# SEQ.net
KiCad netlist of a schematic drawn in Altium Designer
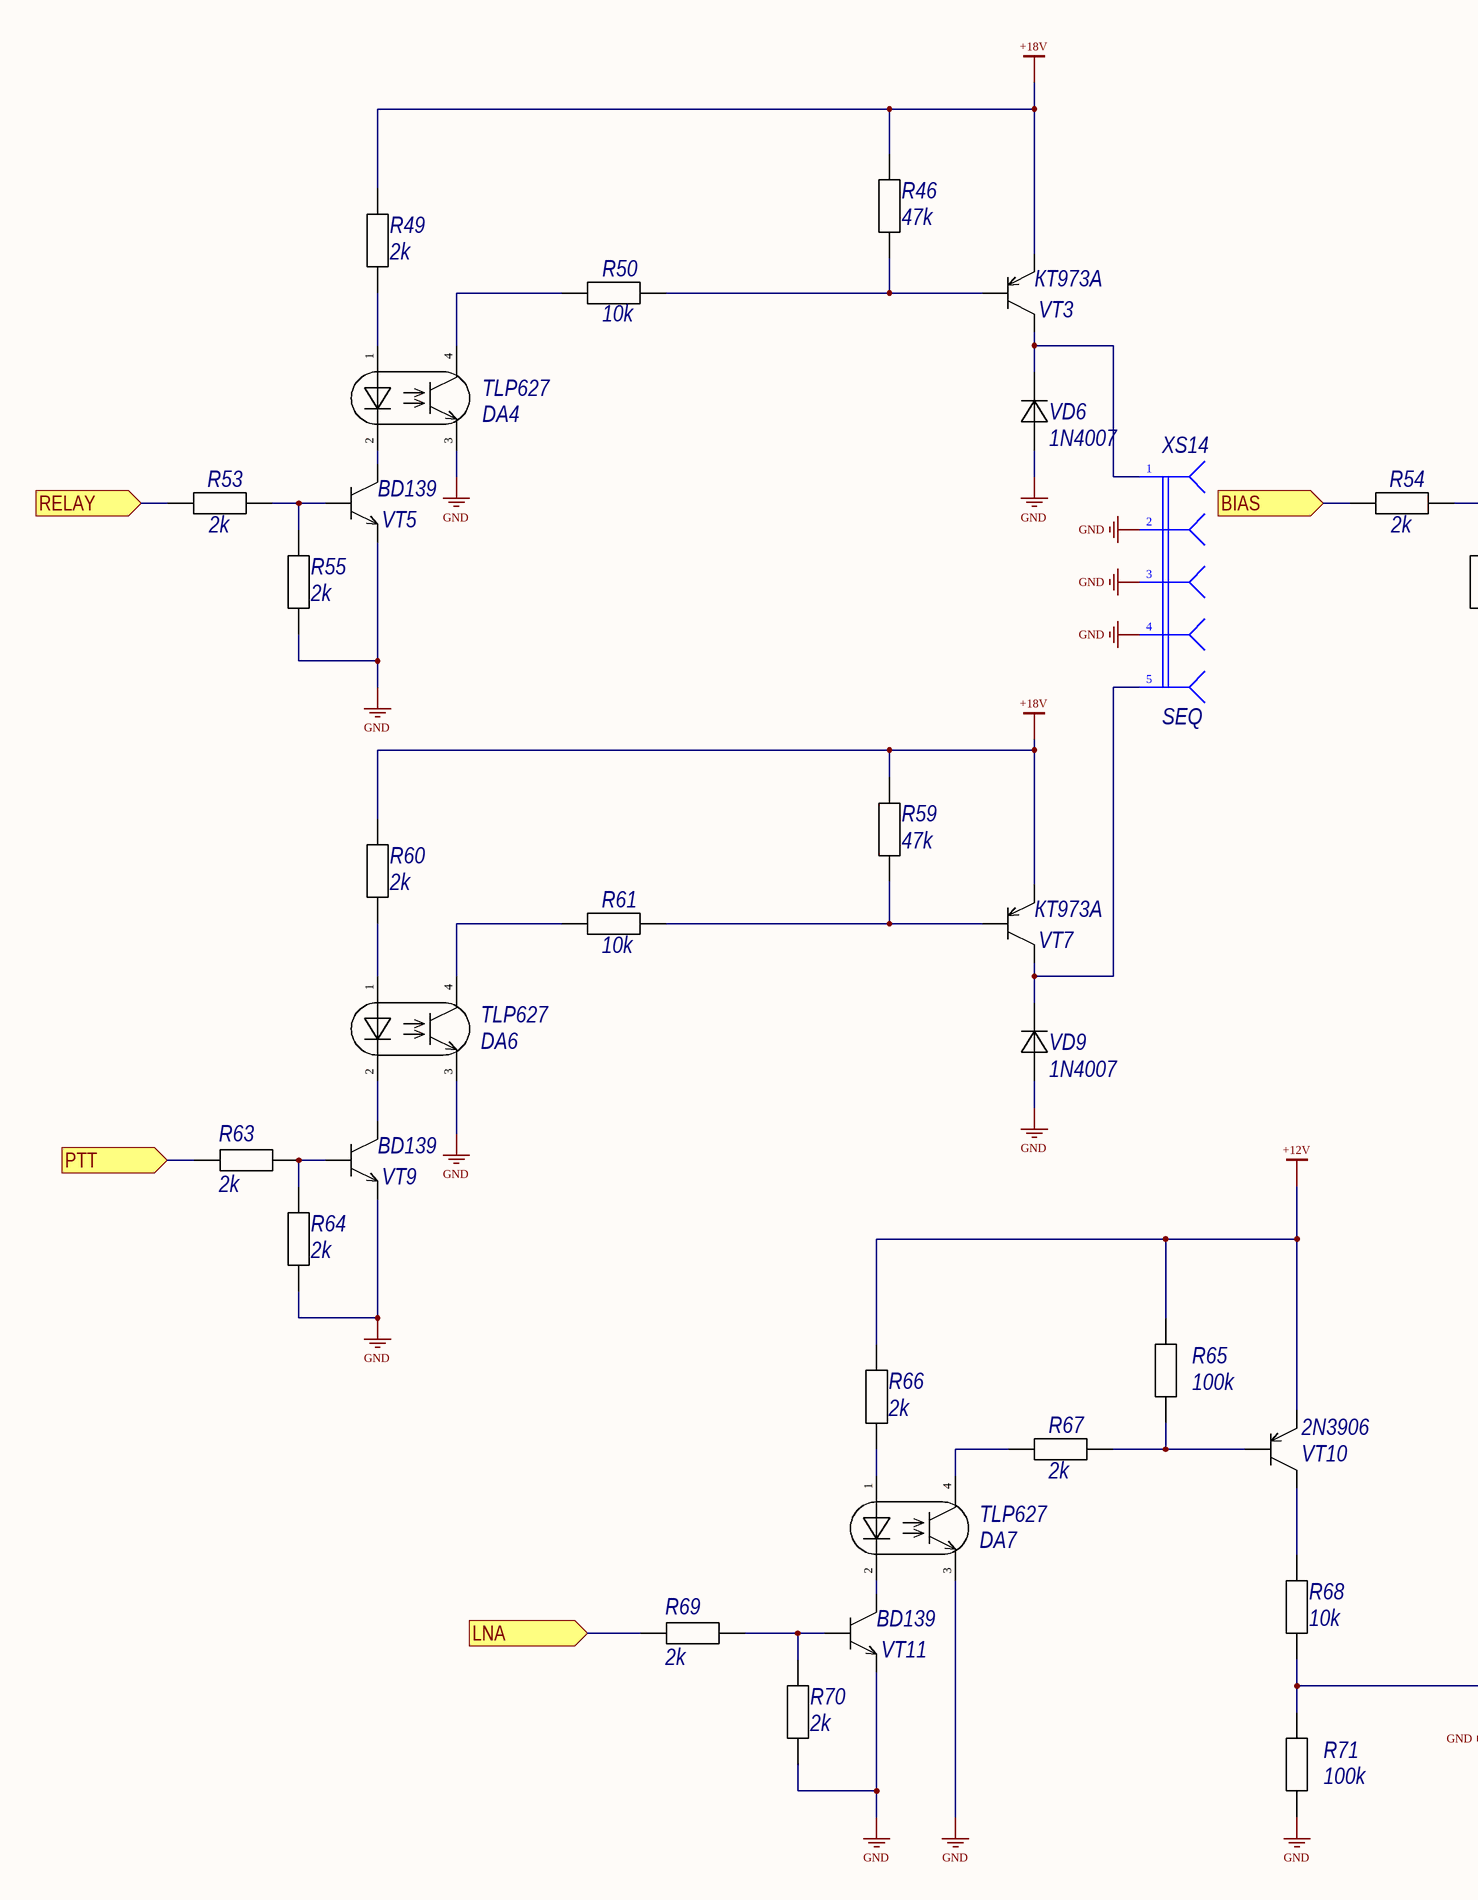
[diagram p0: SEQ.SchDoc, left]
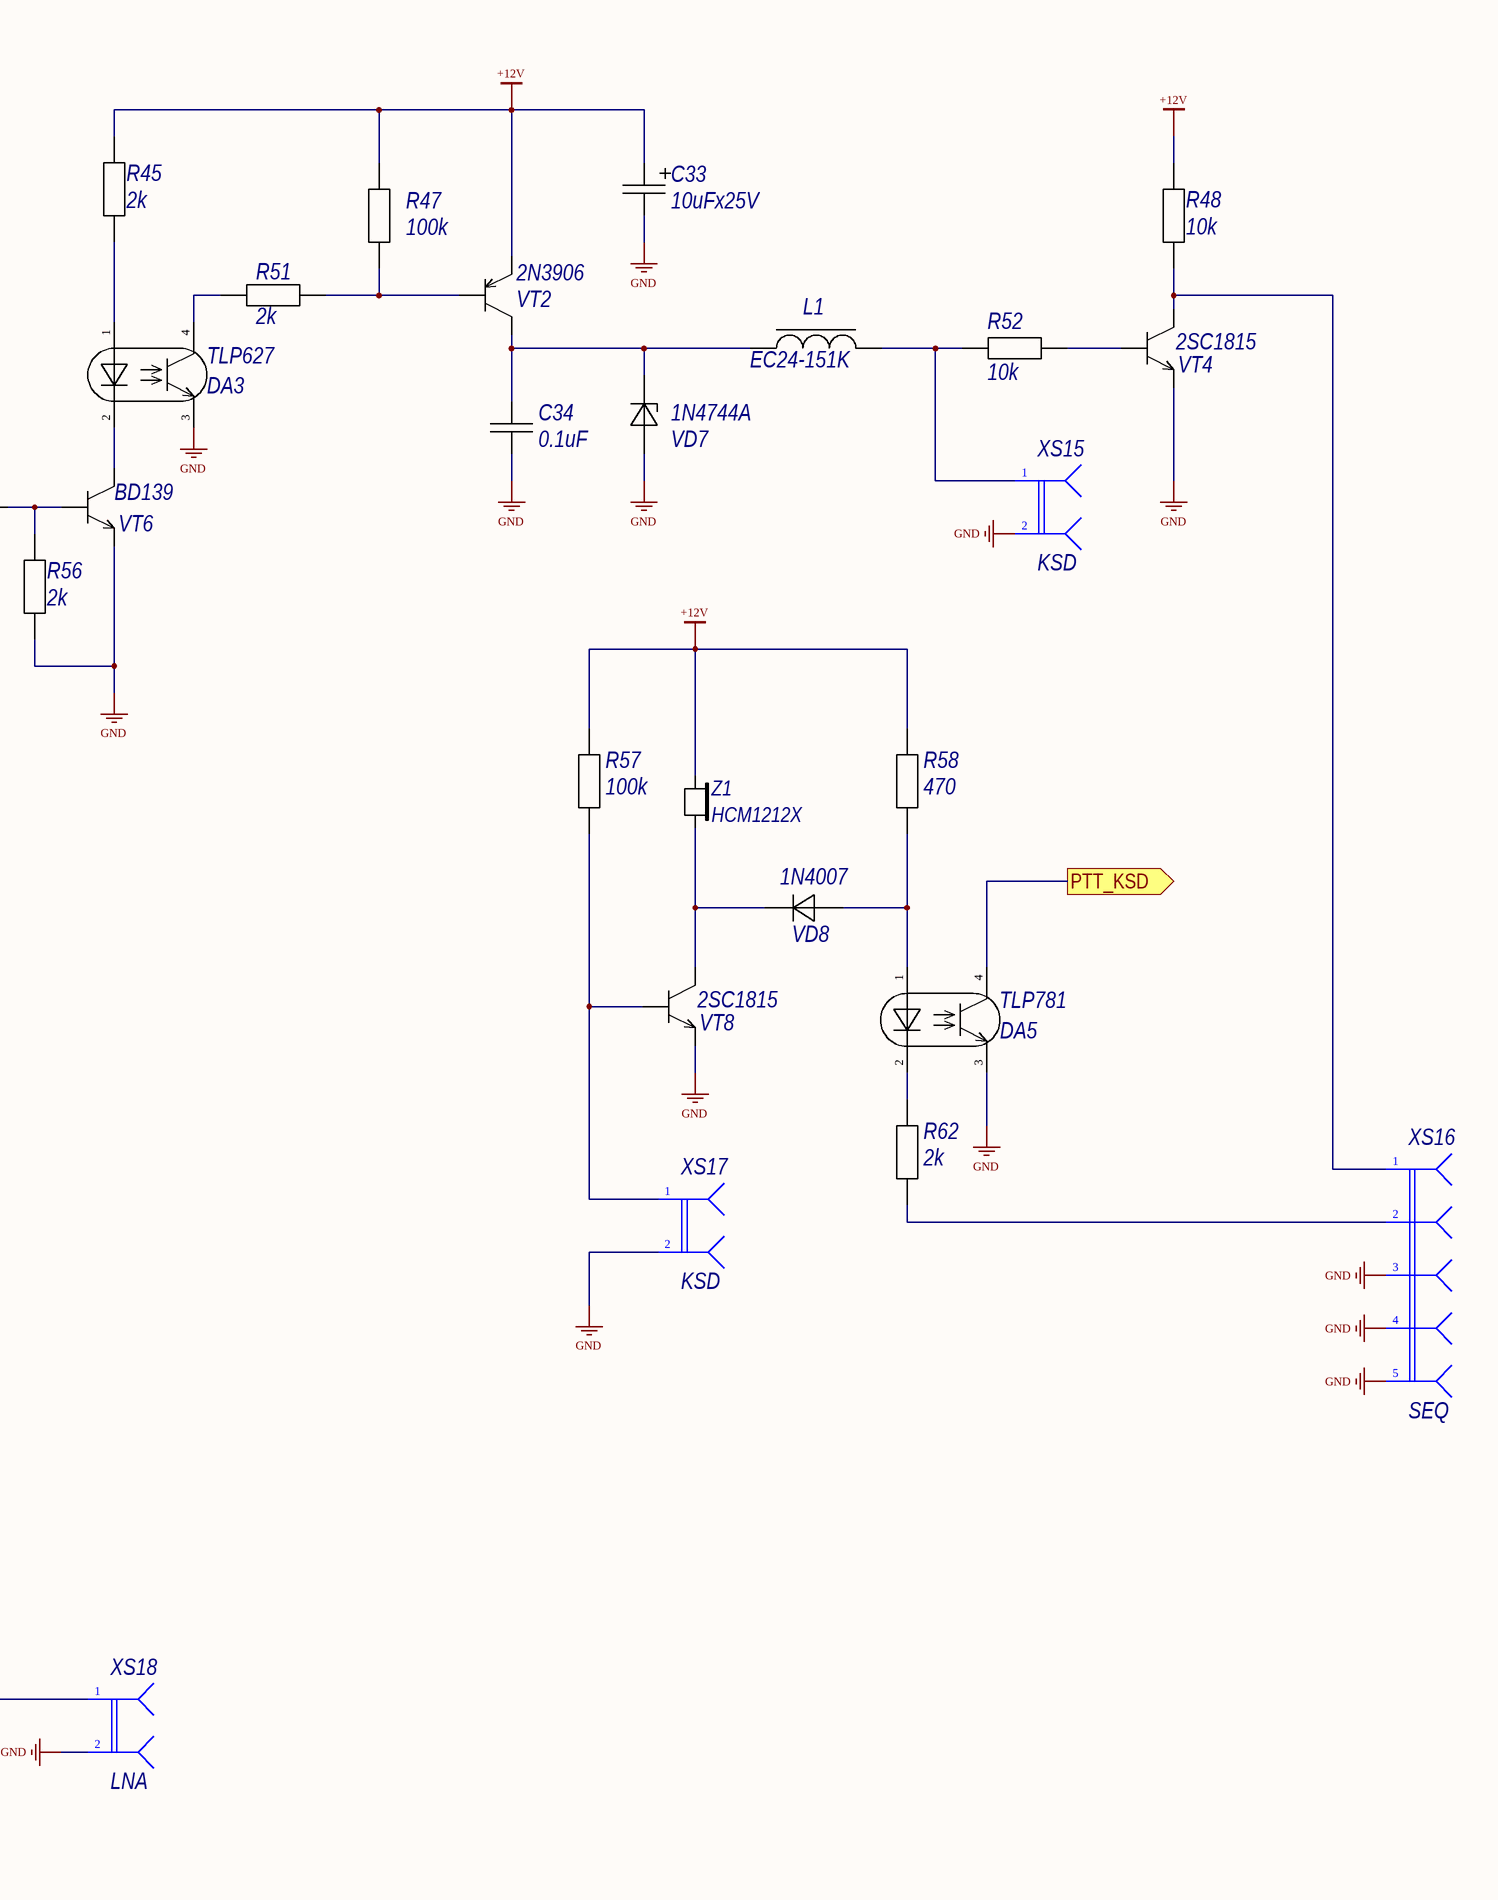
[diagram p1: SEQ.SchDoc, right]

(export (version "E")
  (design (tool "Eeschema 10.0.6"))
  (components
    (comp (ref "C33")
      (value "10uFx25V")
      (footprint "TECAP_A")
      (fields (field (name "PUBLISHER") "Andrew Danich"))
      (libsource (lib "PA_control_board") (part "CAP_TECAP_A"))
    )
    (comp (ref "C34")
      (value "0.1uF")
      (footprint "C0805C")
      (fields (field (name "PUBLISHER") "Andrew Danich"))
      (libsource (lib "PA_control_board") (part "CAP_0805"))
    )
    (comp (ref "DA3")
      (value "TLP627")
      (footprint "DIP-4")
      (fields (field (name "PUBLISHER") "Andrew Danich"))
      (libsource (lib "PA_control_board") (part "TLP627"))
    )
    (comp (ref "DA4")
      (value "TLP627")
      (footprint "DIP-4")
      (fields (field (name "PUBLISHER") "Andrew Danich"))
      (libsource (lib "PA_control_board") (part "TLP627"))
    )
    (comp (ref "DA5")
      (value "TLP781")
      (footprint "DIP-4")
      (fields (field (name "PUBLISHER") "Andrew Danich"))
      (libsource (lib "PA_control_board") (part "TLP781"))
    )
    (comp (ref "DA6")
      (value "TLP627")
      (footprint "DIP-4")
      (fields (field (name "PUBLISHER") "Andrew Danich"))
      (libsource (lib "PA_control_board") (part "TLP627"))
    )
    (comp (ref "DA7")
      (value "TLP627")
      (footprint "DIP-4")
      (fields (field (name "PUBLISHER") "Andrew Danich"))
      (libsource (lib "PA_control_board") (part "TLP627"))
    )
    (comp (ref "L1")
      (value "EC24-151K")
      (footprint "AXIAL-0.6")
      (fields (field (name "PUBLISHER") "Andrew Danich"))
      (libsource (lib "PA_control_board") (part "IND_BIAS"))
    )
    (comp (ref "R45")
      (value "2k")
      (footprint "AXIAL-0.6")
      (fields (field (name "PUBLISHER") "Andrew Danich"))
      (libsource (lib "PA_control_board") (part "RES_1W"))
    )
    (comp (ref "R46")
      (value "47k")
      (footprint "AXIAL-0.6")
      (fields (field (name "PUBLISHER") "Andrew Danich"))
      (libsource (lib "PA_control_board") (part "RES_1W"))
    )
    (comp (ref "R47")
      (value "100k")
      (footprint "AXIAL-0.6")
      (fields (field (name "PUBLISHER") "Andrew Danich"))
      (libsource (lib "PA_control_board") (part "RES_1W"))
    )
    (comp (ref "R48")
      (value "10k")
      (footprint "AXIAL-0.6")
      (fields (field (name "PUBLISHER") "Andrew Danich"))
      (libsource (lib "PA_control_board") (part "RES_1W"))
    )
    (comp (ref "R49")
      (value "2k")
      (footprint "AXIAL-0.6")
      (fields (field (name "PUBLISHER") "Andrew Danich"))
      (libsource (lib "PA_control_board") (part "RES_1W"))
    )
    (comp (ref "R50")
      (value "10k")
      (footprint "AXIAL-0.6")
      (fields (field (name "PUBLISHER") "Andrew Danich"))
      (libsource (lib "PA_control_board") (part "RES_1W"))
    )
    (comp (ref "R51")
      (value "2k")
      (footprint "AXIAL-0.6")
      (fields (field (name "PUBLISHER") "Andrew Danich"))
      (libsource (lib "PA_control_board") (part "RES_1W"))
    )
    (comp (ref "R52")
      (value "10k")
      (footprint "AXIAL-0.6")
      (fields (field (name "PUBLISHER") "Andrew Danich"))
      (libsource (lib "PA_control_board") (part "RES_1W"))
    )
    (comp (ref "R53")
      (value "2k")
      (footprint "AXIAL-0.6")
      (fields (field (name "PUBLISHER") "Andrew Danich"))
      (libsource (lib "PA_control_board") (part "RES_1W"))
    )
    (comp (ref "R54")
      (value "2k")
      (footprint "AXIAL-0.6")
      (fields (field (name "PUBLISHER") "Andrew Danich"))
      (libsource (lib "PA_control_board") (part "RES_1W"))
    )
    (comp (ref "R55")
      (value "2k")
      (footprint "AXIAL-0.6")
      (fields (field (name "PUBLISHER") "Andrew Danich"))
      (libsource (lib "PA_control_board") (part "RES_1W"))
    )
    (comp (ref "R56")
      (value "2k")
      (footprint "AXIAL-0.6")
      (fields (field (name "PUBLISHER") "Andrew Danich"))
      (libsource (lib "PA_control_board") (part "RES_1W"))
    )
    (comp (ref "R57")
      (value "100k")
      (footprint "AXIAL-0.6")
      (fields (field (name "PUBLISHER") "Andrew Danich"))
      (libsource (lib "PA_control_board") (part "RES_1W"))
    )
    (comp (ref "R58")
      (value "470")
      (footprint "AXIAL-0.6")
      (fields (field (name "PUBLISHER") "Andrew Danich"))
      (libsource (lib "PA_control_board") (part "RES_1W"))
    )
    (comp (ref "R59")
      (value "47k")
      (footprint "AXIAL-0.6")
      (fields (field (name "PUBLISHER") "Andrew Danich"))
      (libsource (lib "PA_control_board") (part "RES_1W"))
    )
    (comp (ref "R60")
      (value "2k")
      (footprint "AXIAL-0.6")
      (fields (field (name "PUBLISHER") "Andrew Danich"))
      (libsource (lib "PA_control_board") (part "RES_1W"))
    )
    (comp (ref "R61")
      (value "10k")
      (footprint "AXIAL-0.6")
      (fields (field (name "PUBLISHER") "Andrew Danich"))
      (libsource (lib "PA_control_board") (part "RES_1W"))
    )
    (comp (ref "R62")
      (value "2k")
      (footprint "AXIAL-0.6")
      (fields (field (name "PUBLISHER") "Andrew Danich"))
      (libsource (lib "PA_control_board") (part "RES_1W"))
    )
    (comp (ref "R63")
      (value "2k")
      (footprint "AXIAL-0.6")
      (fields (field (name "PUBLISHER") "Andrew Danich"))
      (libsource (lib "PA_control_board") (part "RES_1W"))
    )
    (comp (ref "R64")
      (value "2k")
      (footprint "AXIAL-0.6")
      (fields (field (name "PUBLISHER") "Andrew Danich"))
      (libsource (lib "PA_control_board") (part "RES_1W"))
    )
    (comp (ref "R65")
      (value "100k")
      (footprint "AXIAL-0.6")
      (fields (field (name "PUBLISHER") "Andrew Danich"))
      (libsource (lib "PA_control_board") (part "RES_1W"))
    )
    (comp (ref "R66")
      (value "2k")
      (footprint "AXIAL-0.6")
      (fields (field (name "PUBLISHER") "Andrew Danich"))
      (libsource (lib "PA_control_board") (part "RES_1W"))
    )
    (comp (ref "R67")
      (value "2k")
      (footprint "AXIAL-0.6")
      (fields (field (name "PUBLISHER") "Andrew Danich"))
      (libsource (lib "PA_control_board") (part "RES_1W"))
    )
    (comp (ref "R68")
      (value "10k")
      (footprint "AXIAL-0.6")
      (fields (field (name "PUBLISHER") "Andrew Danich"))
      (libsource (lib "PA_control_board") (part "RES_1W"))
    )
    (comp (ref "R69")
      (value "2k")
      (footprint "AXIAL-0.6")
      (fields (field (name "PUBLISHER") "Andrew Danich"))
      (libsource (lib "PA_control_board") (part "RES_1W"))
    )
    (comp (ref "R70")
      (value "2k")
      (footprint "AXIAL-0.6")
      (fields (field (name "PUBLISHER") "Andrew Danich"))
      (libsource (lib "PA_control_board") (part "RES_1W"))
    )
    (comp (ref "R71")
      (value "100k")
      (footprint "AXIAL-0.6")
      (fields (field (name "PUBLISHER") "Andrew Danich"))
      (libsource (lib "PA_control_board") (part "RES_1W"))
    )
    (comp (ref "VD6")
      (value "1N4007")
      (footprint "DO-41")
      (fields (field (name "PUBLISHER") "Andrew Danich"))
      (libsource (lib "PA_control_board") (part "1N4007"))
    )
    (comp (ref "VD7")
      (value "1N4744A")
      (footprint "DO-41")
      (fields (field (name "PUBLISHER") "Andrew Danich"))
      (libsource (lib "PA_control_board") (part "1N4744A"))
    )
    (comp (ref "VD8")
      (value "1N4007")
      (footprint "DO-41")
      (fields (field (name "PUBLISHER") "Andrew Danich"))
      (libsource (lib "PA_control_board") (part "1N4007"))
    )
    (comp (ref "VD9")
      (value "1N4007")
      (footprint "DO-41")
      (fields (field (name "PUBLISHER") "Andrew Danich"))
      (libsource (lib "PA_control_board") (part "1N4007"))
    )
    (comp (ref "VT2")
      (value "2N3906")
      (footprint "TO-92-A")
      (fields (field (name "PUBLISHER") "Andrew Danich"))
      (libsource (lib "PA_control_board") (part "2N3906"))
    )
    (comp (ref "VT3")
      (value "КТ973А")
      (footprint "TO-126")
      (fields (field (name "PUBLISHER") "Andrew Danich"))
      (libsource (lib "PA_control_board") (part "КТ973А"))
    )
    (comp (ref "VT4")
      (value "2SC1815")
      (footprint "TO-92-A")
      (fields (field (name "PUBLISHER") "Andrew Danich"))
      (libsource (lib "PA_control_board") (part "2SC1815"))
    )
    (comp (ref "VT5")
      (value "BD139")
      (footprint "TO-126")
      (fields (field (name "PUBLISHER") "Andrew Danich"))
      (libsource (lib "PA_control_board") (part "BD139"))
    )
    (comp (ref "VT6")
      (value "BD139")
      (footprint "TO-126")
      (fields (field (name "PUBLISHER") "Andrew Danich"))
      (libsource (lib "PA_control_board") (part "BD139"))
    )
    (comp (ref "VT7")
      (value "КТ973А")
      (footprint "TO-126")
      (fields (field (name "PUBLISHER") "Andrew Danich"))
      (libsource (lib "PA_control_board") (part "КТ973А"))
    )
    (comp (ref "VT8")
      (value "2SC1815")
      (footprint "TO-92-A")
      (fields (field (name "PUBLISHER") "Andrew Danich"))
      (libsource (lib "PA_control_board") (part "2SC1815"))
    )
    (comp (ref "VT9")
      (value "BD139")
      (footprint "TO-126")
      (fields (field (name "PUBLISHER") "Andrew Danich"))
      (libsource (lib "PA_control_board") (part "BD139"))
    )
    (comp (ref "VT10")
      (value "2N3906")
      (footprint "TO-92-A")
      (fields (field (name "PUBLISHER") "Andrew Danich"))
      (libsource (lib "PA_control_board") (part "2N3906"))
    )
    (comp (ref "VT11")
      (value "BD139")
      (footprint "TO-126")
      (fields (field (name "PUBLISHER") "Andrew Danich"))
      (libsource (lib "PA_control_board") (part "BD139"))
    )
    (comp (ref "XS14")
      (value "SEQ")
      (footprint "WF-5")
      (fields (field (name "PUBLISHER") "Andrew Danich"))
      (libsource (lib "PA_control_board") (part "CONNECT_SEQ"))
    )
    (comp (ref "XS15")
      (value "KSD")
      (footprint "WF-2")
      (fields (field (name "PUBLISHER") "Andrew Danich"))
      (libsource (lib "PA_control_board") (part "CONNECT_KSD"))
    )
    (comp (ref "XS16")
      (value "SEQ")
      (footprint "WF-5")
      (fields (field (name "PUBLISHER") "Andrew Danich"))
      (libsource (lib "PA_control_board") (part "CONNECT_SEQ"))
    )
    (comp (ref "XS17")
      (value "KSD")
      (footprint "WF-2")
      (fields (field (name "PUBLISHER") "Andrew Danich"))
      (libsource (lib "PA_control_board") (part "CONNECT_KSD"))
    )
    (comp (ref "XS18")
      (value "LNA")
      (footprint "WF-2")
      (fields (field (name "PUBLISHER") "Andrew Danich"))
      (libsource (lib "PA_control_board") (part "CONNECT_KSD"))
    )
    (comp (ref "Z1")
      (value "HCM1212X")
      (footprint "HCM1206X")
      (libsource (lib "PA_control_board") (part "HCM1212X"))
    )
  )
  (nets
    (net (code "1") (name "+12V") (class "Default")
      (node (ref "C33") (pin "1") (pinfunction "1_1") (pintype "passive"))
      (node (ref "R45") (pin "2") (pinfunction "2_2") (pintype "passive"))
      (node (ref "R47") (pin "1") (pinfunction "1_1") (pintype "passive"))
      (node (ref "R48") (pin "2") (pinfunction "2_2") (pintype "passive"))
      (node (ref "R57") (pin "2") (pinfunction "2_2") (pintype "passive"))
      (node (ref "R58") (pin "2") (pinfunction "2_2") (pintype "passive"))
      (node (ref "R65") (pin "1") (pinfunction "1_1") (pintype "passive"))
      (node (ref "R66") (pin "2") (pinfunction "2_2") (pintype "passive"))
      (node (ref "VT10") (pin "3") (pinfunction "Э_3") (pintype "passive"))
      (node (ref "VT2") (pin "3") (pinfunction "Э_3") (pintype "passive"))
      (node (ref "Z1") (pin "2") (pinfunction "2_2") (pintype "passive"))
    )
    (net (code "2") (name "+18V") (class "Default")
      (node (ref "R46") (pin "1") (pinfunction "1_1") (pintype "passive"))
      (node (ref "R49") (pin "2") (pinfunction "2_2") (pintype "passive"))
      (node (ref "R59") (pin "1") (pinfunction "1_1") (pintype "passive"))
      (node (ref "R60") (pin "2") (pinfunction "2_2") (pintype "passive"))
      (node (ref "VT3") (pin "3") (pinfunction "Э_3") (pintype "passive"))
      (node (ref "VT7") (pin "3") (pinfunction "Э_3") (pintype "passive"))
    )
    (net (code "3") (name "/BIAS") (class "Default")
      (node (ref "R54") (pin "2") (pinfunction "2_2") (pintype "passive"))
    )
    (net (code "4") (name "/LNA") (class "Default")
      (node (ref "R69") (pin "2") (pinfunction "2_2") (pintype "passive"))
    )
    (net (code "5") (name "/PTT") (class "Default")
      (node (ref "R63") (pin "2") (pinfunction "2_2") (pintype "passive"))
    )
    (net (code "6") (name "/PTT_KSD") (class "Default")
      (node (ref "DA5") (pin "4") (pinfunction "К_4") (pintype "passive"))
    )
    (net (code "7") (name "/RELAY") (class "Default")
      (node (ref "R53") (pin "2") (pinfunction "2_2") (pintype "passive"))
    )
    (net (code "8") (name "GND") (class "Default")
      (node (ref "C33") (pin "2") (pinfunction "2_2") (pintype "passive"))
      (node (ref "C34") (pin "2") (pinfunction "2_2") (pintype "passive"))
      (node (ref "DA3") (pin "3") (pinfunction "Э_3") (pintype "passive"))
      (node (ref "DA4") (pin "3") (pinfunction "Э_3") (pintype "passive"))
      (node (ref "DA5") (pin "3") (pinfunction "Э_3") (pintype "passive"))
      (node (ref "DA6") (pin "3") (pinfunction "Э_3") (pintype "passive"))
      (node (ref "DA7") (pin "3") (pinfunction "Э_3") (pintype "passive"))
      (node (ref "R55") (pin "1") (pinfunction "1_1") (pintype "passive"))
      (node (ref "R56") (pin "1") (pinfunction "1_1") (pintype "passive"))
      (node (ref "R64") (pin "1") (pinfunction "1_1") (pintype "passive"))
      (node (ref "R70") (pin "1") (pinfunction "1_1") (pintype "passive"))
      (node (ref "R71") (pin "2") (pinfunction "2_2") (pintype "passive"))
      (node (ref "VD6") (pin "2") (pinfunction "2_2") (pintype "passive"))
      (node (ref "VD7") (pin "1") (pinfunction "А_1") (pintype "passive"))
      (node (ref "VD9") (pin "2") (pinfunction "2_2") (pintype "passive"))
      (node (ref "VT11") (pin "3") (pinfunction "Э_3") (pintype "passive"))
      (node (ref "VT4") (pin "3") (pinfunction "Э_3") (pintype "passive"))
      (node (ref "VT5") (pin "3") (pinfunction "Э_3") (pintype "passive"))
      (node (ref "VT6") (pin "3") (pinfunction "Э_3") (pintype "passive"))
      (node (ref "VT8") (pin "3") (pinfunction "Э_3") (pintype "passive"))
      (node (ref "VT9") (pin "3") (pinfunction "Э_3") (pintype "passive"))
      (node (ref "XS14") (pin "2") (pintype "passive"))
      (node (ref "XS14") (pin "3") (pintype "passive"))
      (node (ref "XS14") (pin "4") (pintype "passive"))
      (node (ref "XS15") (pin "2") (pintype "passive"))
      (node (ref "XS16") (pin "3") (pintype "passive"))
      (node (ref "XS16") (pin "4") (pintype "passive"))
      (node (ref "XS16") (pin "5") (pintype "passive"))
      (node (ref "XS17") (pin "2") (pintype "passive"))
      (node (ref "XS18") (pin "2") (pintype "passive"))
    )
    (net (code "9") (name "Net-(DA3-CА)") (class "Default")
      (node (ref "DA3") (pin "1") (pinfunction "CА_1") (pintype "passive"))
      (node (ref "R45") (pin "1") (pinfunction "1_1") (pintype "passive"))
    )
    (net (code "10") (name "Net-(DA3-CК)") (class "Default")
      (node (ref "DA3") (pin "2") (pinfunction "CК_2") (pintype "passive"))
      (node (ref "VT6") (pin "2") (pinfunction "К_2") (pintype "passive"))
    )
    (net (code "11") (name "Net-(DA3-К)") (class "Default")
      (node (ref "DA3") (pin "4") (pinfunction "К_4") (pintype "passive"))
      (node (ref "R51") (pin "2") (pinfunction "2_2") (pintype "passive"))
    )
    (net (code "12") (name "Net-(DA4-CА)") (class "Default")
      (node (ref "DA4") (pin "1") (pinfunction "CА_1") (pintype "passive"))
      (node (ref "R49") (pin "1") (pinfunction "1_1") (pintype "passive"))
    )
    (net (code "13") (name "Net-(DA4-CК)") (class "Default")
      (node (ref "DA4") (pin "2") (pinfunction "CК_2") (pintype "passive"))
      (node (ref "VT5") (pin "2") (pinfunction "К_2") (pintype "passive"))
    )
    (net (code "14") (name "Net-(DA4-К)") (class "Default")
      (node (ref "DA4") (pin "4") (pinfunction "К_4") (pintype "passive"))
      (node (ref "R50") (pin "2") (pinfunction "2_2") (pintype "passive"))
    )
    (net (code "15") (name "Net-(DA5-CА)") (class "Default")
      (node (ref "DA5") (pin "1") (pinfunction "CА_1") (pintype "passive"))
      (node (ref "R58") (pin "1") (pinfunction "1_1") (pintype "passive"))
      (node (ref "VD8") (pin "2") (pinfunction "2_2") (pintype "passive"))
    )
    (net (code "16") (name "Net-(DA5-CК)") (class "Default")
      (node (ref "DA5") (pin "2") (pinfunction "CК_2") (pintype "passive"))
      (node (ref "R62") (pin "2") (pinfunction "2_2") (pintype "passive"))
    )
    (net (code "17") (name "Net-(DA6-CА)") (class "Default")
      (node (ref "DA6") (pin "1") (pinfunction "CА_1") (pintype "passive"))
      (node (ref "R60") (pin "1") (pinfunction "1_1") (pintype "passive"))
    )
    (net (code "18") (name "Net-(DA6-CК)") (class "Default")
      (node (ref "DA6") (pin "2") (pinfunction "CК_2") (pintype "passive"))
      (node (ref "VT9") (pin "2") (pinfunction "К_2") (pintype "passive"))
    )
    (net (code "19") (name "Net-(DA6-К)") (class "Default")
      (node (ref "DA6") (pin "4") (pinfunction "К_4") (pintype "passive"))
      (node (ref "R61") (pin "2") (pinfunction "2_2") (pintype "passive"))
    )
    (net (code "20") (name "Net-(DA7-CА)") (class "Default")
      (node (ref "DA7") (pin "1") (pinfunction "CА_1") (pintype "passive"))
      (node (ref "R66") (pin "1") (pinfunction "1_1") (pintype "passive"))
    )
    (net (code "21") (name "Net-(DA7-CК)") (class "Default")
      (node (ref "DA7") (pin "2") (pinfunction "CК_2") (pintype "passive"))
      (node (ref "VT11") (pin "2") (pinfunction "К_2") (pintype "passive"))
    )
    (net (code "22") (name "Net-(DA7-К)") (class "Default")
      (node (ref "DA7") (pin "4") (pinfunction "К_4") (pintype "passive"))
      (node (ref "R67") (pin "2") (pinfunction "2_2") (pintype "passive"))
    )
    (net (code "23") (name "Net-(L1-Pad2)") (class "Default")
      (node (ref "L1") (pin "2") (pinfunction "2_2") (pintype "passive"))
      (node (ref "R52") (pin "1") (pinfunction "1_1") (pintype "passive"))
      (node (ref "XS15") (pin "1") (pintype "passive"))
    )
    (net (code "24") (name "Net-(R62-Pad1)") (class "Default")
      (node (ref "R62") (pin "1") (pinfunction "1_1") (pintype "passive"))
      (node (ref "XS16") (pin "2") (pintype "passive"))
    )
    (net (code "25") (name "Net-(R68-Pad1)") (class "Default")
      (node (ref "R68") (pin "1") (pinfunction "1_1") (pintype "passive"))
      (node (ref "R71") (pin "1") (pinfunction "1_1") (pintype "passive"))
      (node (ref "XS18") (pin "1") (pintype "passive"))
    )
    (net (code "26") (name "Net-(VD7-К)") (class "Default")
      (node (ref "C34") (pin "1") (pinfunction "1_1") (pintype "passive"))
      (node (ref "L1") (pin "1") (pinfunction "1_1") (pintype "passive"))
      (node (ref "VD7") (pin "2") (pinfunction "К_2") (pintype "passive"))
      (node (ref "VT2") (pin "2") (pinfunction "К_2") (pintype "passive"))
    )
    (net (code "27") (name "Net-(VT2-Б)") (class "Default")
      (node (ref "R47") (pin "2") (pinfunction "2_2") (pintype "passive"))
      (node (ref "R51") (pin "1") (pinfunction "1_1") (pintype "passive"))
      (node (ref "VT2") (pin "1") (pinfunction "Б_1") (pintype "passive"))
    )
    (net (code "28") (name "Net-(VT3-Б)") (class "Default")
      (node (ref "R46") (pin "2") (pinfunction "2_2") (pintype "passive"))
      (node (ref "R50") (pin "1") (pinfunction "1_1") (pintype "passive"))
      (node (ref "VT3") (pin "1") (pinfunction "Б_1") (pintype "passive"))
    )
    (net (code "29") (name "Net-(VT3-К)") (class "Default")
      (node (ref "VD6") (pin "1") (pinfunction "1_1") (pintype "passive"))
      (node (ref "VT3") (pin "2") (pinfunction "К_2") (pintype "passive"))
      (node (ref "XS14") (pin "1") (pintype "passive"))
    )
    (net (code "30") (name "Net-(VT4-Б)") (class "Default")
      (node (ref "R52") (pin "2") (pinfunction "2_2") (pintype "passive"))
      (node (ref "VT4") (pin "1") (pinfunction "Б_1") (pintype "passive"))
    )
    (net (code "31") (name "Net-(VT4-К)") (class "Default")
      (node (ref "R48") (pin "1") (pinfunction "1_1") (pintype "passive"))
      (node (ref "VT4") (pin "2") (pinfunction "К_2") (pintype "passive"))
      (node (ref "XS16") (pin "1") (pintype "passive"))
    )
    (net (code "32") (name "Net-(VT5-Б)") (class "Default")
      (node (ref "R53") (pin "1") (pinfunction "1_1") (pintype "passive"))
      (node (ref "R55") (pin "2") (pinfunction "2_2") (pintype "passive"))
      (node (ref "VT5") (pin "1") (pinfunction "Б_1") (pintype "passive"))
    )
    (net (code "33") (name "Net-(VT6-Б)") (class "Default")
      (node (ref "R54") (pin "1") (pinfunction "1_1") (pintype "passive"))
      (node (ref "R56") (pin "2") (pinfunction "2_2") (pintype "passive"))
      (node (ref "VT6") (pin "1") (pinfunction "Б_1") (pintype "passive"))
    )
    (net (code "34") (name "Net-(VT7-Б)") (class "Default")
      (node (ref "R59") (pin "2") (pinfunction "2_2") (pintype "passive"))
      (node (ref "R61") (pin "1") (pinfunction "1_1") (pintype "passive"))
      (node (ref "VT7") (pin "1") (pinfunction "Б_1") (pintype "passive"))
    )
    (net (code "35") (name "Net-(VT7-К)") (class "Default")
      (node (ref "VD9") (pin "1") (pinfunction "1_1") (pintype "passive"))
      (node (ref "VT7") (pin "2") (pinfunction "К_2") (pintype "passive"))
      (node (ref "XS14") (pin "5") (pintype "passive"))
    )
    (net (code "36") (name "Net-(VT8-Б)") (class "Default")
      (node (ref "R57") (pin "1") (pinfunction "1_1") (pintype "passive"))
      (node (ref "VT8") (pin "1") (pinfunction "Б_1") (pintype "passive"))
      (node (ref "XS17") (pin "1") (pintype "passive"))
    )
    (net (code "37") (name "Net-(VT8-К)") (class "Default")
      (node (ref "VD8") (pin "1") (pinfunction "1_1") (pintype "passive"))
      (node (ref "VT8") (pin "2") (pinfunction "К_2") (pintype "passive"))
      (node (ref "Z1") (pin "1") (pinfunction "1_1") (pintype "passive"))
    )
    (net (code "38") (name "Net-(VT9-Б)") (class "Default")
      (node (ref "R63") (pin "1") (pinfunction "1_1") (pintype "passive"))
      (node (ref "R64") (pin "2") (pinfunction "2_2") (pintype "passive"))
      (node (ref "VT9") (pin "1") (pinfunction "Б_1") (pintype "passive"))
    )
    (net (code "39") (name "Net-(VT10-Б)") (class "Default")
      (node (ref "R65") (pin "2") (pinfunction "2_2") (pintype "passive"))
      (node (ref "R67") (pin "1") (pinfunction "1_1") (pintype "passive"))
      (node (ref "VT10") (pin "1") (pinfunction "Б_1") (pintype "passive"))
    )
    (net (code "40") (name "Net-(VT10-К)") (class "Default")
      (node (ref "R68") (pin "2") (pinfunction "2_2") (pintype "passive"))
      (node (ref "VT10") (pin "2") (pinfunction "К_2") (pintype "passive"))
    )
    (net (code "41") (name "Net-(VT11-Б)") (class "Default")
      (node (ref "R69") (pin "1") (pinfunction "1_1") (pintype "passive"))
      (node (ref "R70") (pin "2") (pinfunction "2_2") (pintype "passive"))
      (node (ref "VT11") (pin "1") (pinfunction "Б_1") (pintype "passive"))
    )
  )
)
